# chuckwagon.net
KiCad netlist of a schematic drawn in EAGLE
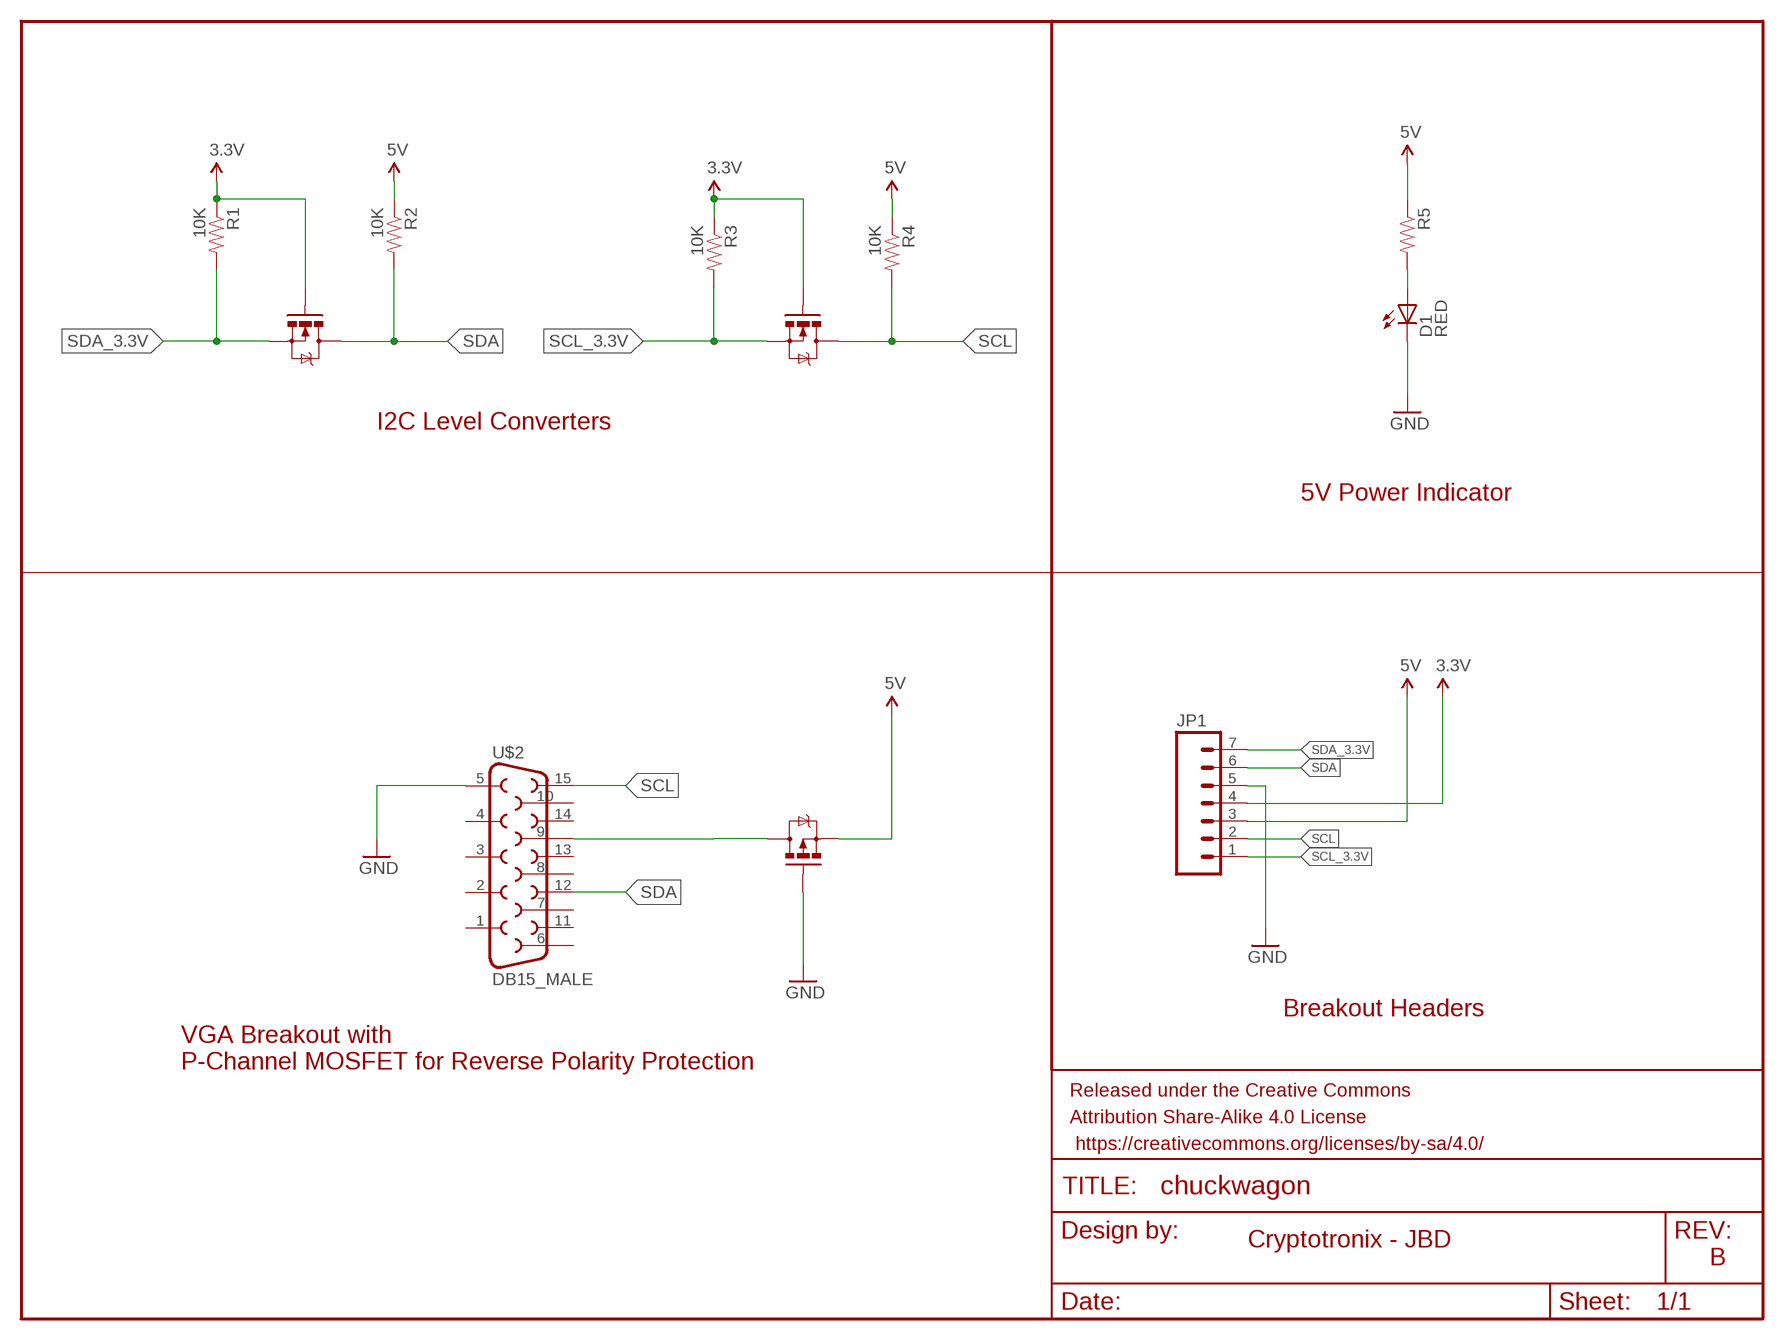
[diagram p0: schematic, sheet 1]

(export (version "E")
  (design (tool "Eeschema 10.0.6"))
  (components
    (comp (ref "D1")
      (value "RED")
      (footprint "eagle-import:LED-0603")
      (libsource (lib "eagle-import") (part "LED-RED0603"))
    )
    (comp (ref "FRAME1")
      (value "FRAME-LETTER")
      (footprint "eagle-import:CREATIVE_COMMONS")
      (libsource (lib "eagle-import") (part "FRAME-LETTER"))
    )
    (comp (ref "JP1")
      (value "M07")
      (footprint "eagle-import:1X07")
      (libsource (lib "eagle-import") (part "M07"))
    )
    (comp (ref "Q1")
      (value "MOSFET-NCHANNELBSS123LT1G")
      (footprint "eagle-import:SOT23")
      (libsource (lib "eagle-import") (part "MOSFET-NCHANNELBSS123LT1G"))
    )
    (comp (ref "Q2")
      (value "MOSFET-NCHANNELBSS123LT1G")
      (footprint "eagle-import:SOT23")
      (libsource (lib "eagle-import") (part "MOSFET-NCHANNELBSS123LT1G"))
    )
    (comp (ref "Q3")
      (value "MOSFET-PCHANNEL")
      (footprint "eagle-import:SOT23-3")
      (libsource (lib "eagle-import") (part "MOSFET-PCHANNEL"))
    )
    (comp (ref "R1")
      (value "10K")
      (footprint "eagle-import:0603-RES")
      (libsource (lib "eagle-import") (part "RESISTOR0603-RES"))
    )
    (comp (ref "R2")
      (value "10K")
      (footprint "eagle-import:0603-RES")
      (libsource (lib "eagle-import") (part "RESISTOR0603-RES"))
    )
    (comp (ref "R3")
      (value "10K")
      (footprint "eagle-import:0603-RES")
      (libsource (lib "eagle-import") (part "RESISTOR0603-RES"))
    )
    (comp (ref "R4")
      (value "10K")
      (footprint "eagle-import:0603-RES")
      (libsource (lib "eagle-import") (part "RESISTOR0603-RES"))
    )
    (comp (ref "R5")
      (value "RESISTOR0603-RES")
      (footprint "eagle-import:0603-RES")
      (libsource (lib "eagle-import") (part "RESISTOR0603-RES"))
    )
    (comp (ref "U$2")
      (value "DB15_MALE")
      (footprint "eagle-import:DB15_MALE")
      (libsource (lib "eagle-import") (part "DB15_MALE"))
    )
  )
  (nets
    (net (code "1") (name "3.3V") (class "Default")
      (node (ref "JP1") (pin "4") (pinfunction "4_4") (pintype "passive"))
      (node (ref "Q1") (pin "1") (pinfunction "G_1") (pintype "passive"))
      (node (ref "Q2") (pin "1") (pinfunction "G_1") (pintype "passive"))
      (node (ref "R1") (pin "1") (pinfunction "1_1") (pintype "passive"))
      (node (ref "R3") (pin "1") (pinfunction "1_1") (pintype "passive"))
    )
    (net (code "2") (name "5V") (class "Default")
      (node (ref "JP1") (pin "3") (pinfunction "3_3") (pintype "passive"))
      (node (ref "Q3") (pin "2") (pinfunction "S_2") (pintype "passive"))
      (node (ref "R2") (pin "1") (pinfunction "1_1") (pintype "passive"))
      (node (ref "R4") (pin "1") (pinfunction "1_1") (pintype "passive"))
      (node (ref "R5") (pin "1") (pinfunction "1_1") (pintype "passive"))
    )
    (net (code "3") (name "GND") (class "Default")
      (node (ref "D1") (pin "C") (pinfunction "C_C") (pintype "passive"))
      (node (ref "JP1") (pin "5") (pinfunction "5_5") (pintype "passive"))
      (node (ref "Q3") (pin "1") (pinfunction "G_1") (pintype "passive"))
      (node (ref "U$2") (pin "5") (pinfunction "5_5") (pintype "passive"))
    )
    (net (code "4") (name "Net-(D1-PadA)") (class "Default")
      (node (ref "D1") (pin "A") (pinfunction "A_A") (pintype "passive"))
      (node (ref "R5") (pin "2") (pinfunction "2_2") (pintype "passive"))
    )
    (net (code "5") (name "Net-(Q3-D)") (class "Default")
      (node (ref "Q3") (pin "3") (pinfunction "D_3") (pintype "passive"))
      (node (ref "U$2") (pin "9") (pinfunction "9_9") (pintype "passive"))
    )
    (net (code "6") (name "SCL") (class "Default")
      (node (ref "JP1") (pin "2") (pinfunction "2_2") (pintype "passive"))
      (node (ref "Q2") (pin "3") (pinfunction "D_3") (pintype "passive"))
      (node (ref "R4") (pin "2") (pinfunction "2_2") (pintype "passive"))
      (node (ref "U$2") (pin "15") (pinfunction "15_15") (pintype "passive"))
    )
    (net (code "7") (name "SCL_3.3V") (class "Default")
      (node (ref "JP1") (pin "1") (pinfunction "1_1") (pintype "passive"))
      (node (ref "Q2") (pin "2") (pinfunction "S_2") (pintype "passive"))
      (node (ref "R3") (pin "2") (pinfunction "2_2") (pintype "passive"))
    )
    (net (code "8") (name "SDA") (class "Default")
      (node (ref "JP1") (pin "6") (pinfunction "6_6") (pintype "passive"))
      (node (ref "Q1") (pin "3") (pinfunction "D_3") (pintype "passive"))
      (node (ref "R2") (pin "2") (pinfunction "2_2") (pintype "passive"))
      (node (ref "U$2") (pin "12") (pinfunction "12_12") (pintype "passive"))
    )
    (net (code "9") (name "SDA_3.3V") (class "Default")
      (node (ref "JP1") (pin "7") (pinfunction "7_7") (pintype "passive"))
      (node (ref "Q1") (pin "2") (pinfunction "S_2") (pintype "passive"))
      (node (ref "R1") (pin "2") (pinfunction "2_2") (pintype "passive"))
    )
    (net (code "10") (name "unconnected-(U$2-Pad1)") (class "Default")
      (node (ref "U$2") (pin "1") (pinfunction "1_1") (pintype "passive"))
    )
    (net (code "11") (name "unconnected-(U$2-Pad2)") (class "Default")
      (node (ref "U$2") (pin "2") (pinfunction "2_2") (pintype "passive"))
    )
    (net (code "12") (name "unconnected-(U$2-Pad3)") (class "Default")
      (node (ref "U$2") (pin "3") (pinfunction "3_3") (pintype "passive"))
    )
    (net (code "13") (name "unconnected-(U$2-Pad4)") (class "Default")
      (node (ref "U$2") (pin "4") (pinfunction "4_4") (pintype "passive"))
    )
    (net (code "14") (name "unconnected-(U$2-Pad6)") (class "Default")
      (node (ref "U$2") (pin "6") (pinfunction "6_6") (pintype "passive"))
    )
    (net (code "15") (name "unconnected-(U$2-Pad7)") (class "Default")
      (node (ref "U$2") (pin "7") (pinfunction "7_7") (pintype "passive"))
    )
    (net (code "16") (name "unconnected-(U$2-Pad8)") (class "Default")
      (node (ref "U$2") (pin "8") (pinfunction "8_8") (pintype "passive"))
    )
    (net (code "17") (name "unconnected-(U$2-Pad10)") (class "Default")
      (node (ref "U$2") (pin "10") (pinfunction "10_10") (pintype "passive"))
    )
    (net (code "18") (name "unconnected-(U$2-Pad11)") (class "Default")
      (node (ref "U$2") (pin "11") (pinfunction "11_11") (pintype "passive"))
    )
    (net (code "19") (name "unconnected-(U$2-Pad13)") (class "Default")
      (node (ref "U$2") (pin "13") (pinfunction "13_13") (pintype "passive"))
    )
    (net (code "20") (name "unconnected-(U$2-Pad14)") (class "Default")
      (node (ref "U$2") (pin "14") (pinfunction "14_14") (pintype "passive"))
    )
  )
)
